# safeguard.net
KiCad netlist of a schematic drawn in EAGLE
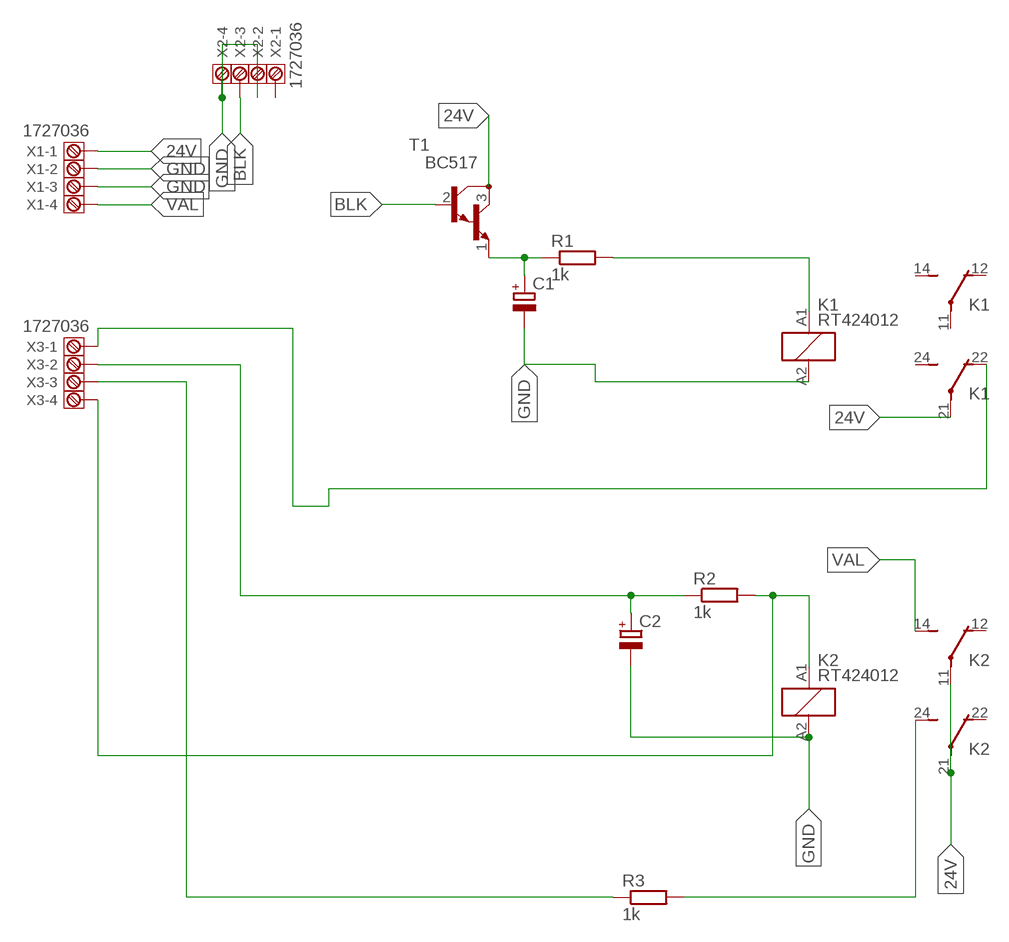
[diagram p0: schematic, sheet 1]

(export (version "E")
  (design (tool "Eeschema 10.0.6"))
  (components
    (comp (ref "C1")
      (value "CPOL-EU153CLV-0405")
      (footprint "eagle-import:153CLV-0405")
      (libsource (lib "eagle-import") (part "CPOL-EU153CLV-0405"))
    )
    (comp (ref "C2")
      (value "CPOL-EU153CLV-0405")
      (footprint "eagle-import:153CLV-0405")
      (libsource (lib "eagle-import") (part "CPOL-EU153CLV-0405"))
    )
    (comp (ref "K1")
      (value "RT424012")
      (footprint "eagle-import:RT2C_O")
      (libsource (lib "eagle-import") (part "RT42?4012"))
    )
    (comp (ref "K2")
      (value "RT424012")
      (footprint "eagle-import:RT2C_O")
      (libsource (lib "eagle-import") (part "RT42?4012"))
    )
    (comp (ref "R1")
      (value "1k")
      (footprint "eagle-import:0204_7")
      (libsource (lib "eagle-import") (part "R-EU_0204/7"))
    )
    (comp (ref "R2")
      (value "1k")
      (footprint "eagle-import:0204_7")
      (libsource (lib "eagle-import") (part "R-EU_0204/7"))
    )
    (comp (ref "R3")
      (value "1k")
      (footprint "eagle-import:0204_7")
      (libsource (lib "eagle-import") (part "R-EU_0204/7"))
    )
    (comp (ref "T1")
      (value "BC517")
      (footprint "eagle-import:TO92")
      (libsource (lib "eagle-import") (part "BC517"))
    )
    (comp (ref "X1")
      (value "1727036")
      (footprint "eagle-import:1727036")
      (fields (field (name "MF") "FARNELL"))
      (libsource (lib "eagle-import") (part "1727036"))
    )
    (comp (ref "X2")
      (value "1727036")
      (footprint "eagle-import:1727036")
      (fields (field (name "MF") "FARNELL"))
      (libsource (lib "eagle-import") (part "1727036"))
    )
    (comp (ref "X3")
      (value "1727036")
      (footprint "eagle-import:1727036")
      (fields (field (name "MF") "FARNELL"))
      (libsource (lib "eagle-import") (part "1727036"))
    )
  )
  (nets
    (net (code "1") (name "24V") (class "Default")
      (node (ref "K1") (pin "21") (pinfunction "P_21") (pintype "passive"))
      (node (ref "K2") (pin "11") (pinfunction "P_11") (pintype "passive"))
      (node (ref "K2") (pin "21") (pinfunction "P_21") (pintype "passive"))
      (node (ref "T1") (pin "3") (pinfunction "C_3") (pintype "passive"))
      (node (ref "X1") (pin "1") (pinfunction "1_1") (pintype "passive"))
    )
    (net (code "2") (name "BLK") (class "Default")
      (node (ref "T1") (pin "2") (pinfunction "B_2") (pintype "passive"))
      (node (ref "X2") (pin "3") (pinfunction "1_3") (pintype "passive"))
    )
    (net (code "3") (name "GND") (class "Default")
      (node (ref "C1") (pin "-") (pinfunction "-_-") (pintype "passive"))
      (node (ref "C2") (pin "-") (pinfunction "-_-") (pintype "passive"))
      (node (ref "K1") (pin "A2") (pinfunction "2_A2") (pintype "passive"))
      (node (ref "K2") (pin "A2") (pinfunction "2_A2") (pintype "passive"))
      (node (ref "X1") (pin "2") (pinfunction "1_2") (pintype "passive"))
      (node (ref "X1") (pin "3") (pinfunction "1_3") (pintype "passive"))
      (node (ref "X2") (pin "2") (pinfunction "1_2") (pintype "passive"))
      (node (ref "X2") (pin "4") (pinfunction "1_4") (pintype "passive"))
    )
    (net (code "4") (name "Net-(K1A-1)") (class "Default")
      (node (ref "K1") (pin "A1") (pinfunction "1_A1") (pintype "passive"))
      (node (ref "R1") (pin "2") (pinfunction "2_2") (pintype "passive"))
    )
    (net (code "5") (name "Net-(K1C-O)") (class "Default")
      (node (ref "K1") (pin "22") (pinfunction "O_22") (pintype "passive"))
      (node (ref "X3") (pin "1") (pinfunction "1_1") (pintype "passive"))
    )
    (net (code "6") (name "Net-(K2A-1)") (class "Default")
      (node (ref "K2") (pin "A1") (pinfunction "1_A1") (pintype "passive"))
      (node (ref "R2") (pin "2") (pinfunction "2_2") (pintype "passive"))
      (node (ref "X3") (pin "4") (pinfunction "1_4") (pintype "passive"))
    )
    (net (code "7") (name "Net-(K2C-S)") (class "Default")
      (node (ref "K2") (pin "24") (pinfunction "S_24") (pintype "passive"))
      (node (ref "R3") (pin "2") (pinfunction "2_2") (pintype "passive"))
    )
    (net (code "8") (name "Net-(T1-E)") (class "Default")
      (node (ref "C1") (pin "+") (pinfunction "+_+") (pintype "passive"))
      (node (ref "R1") (pin "1") (pinfunction "1_1") (pintype "passive"))
      (node (ref "T1") (pin "1") (pinfunction "E_1") (pintype "passive"))
    )
    (net (code "9") (name "Net-(X3B-1)") (class "Default")
      (node (ref "C2") (pin "+") (pinfunction "+_+") (pintype "passive"))
      (node (ref "R2") (pin "1") (pinfunction "1_1") (pintype "passive"))
      (node (ref "X3") (pin "2") (pinfunction "1_2") (pintype "passive"))
    )
    (net (code "10") (name "Net-(X3C-1)") (class "Default")
      (node (ref "R3") (pin "1") (pinfunction "1_1") (pintype "passive"))
      (node (ref "X3") (pin "3") (pinfunction "1_3") (pintype "passive"))
    )
    (net (code "11") (name "VAL") (class "Default")
      (node (ref "K2") (pin "14") (pinfunction "S_14") (pintype "passive"))
      (node (ref "X1") (pin "4") (pinfunction "1_4") (pintype "passive"))
    )
    (net (code "12") (name "unconnected-(K1B-O-Pad12)") (class "Default")
      (node (ref "K1") (pin "12") (pinfunction "O_12") (pintype "passive"))
    )
    (net (code "13") (name "unconnected-(K1B-P-Pad11)") (class "Default")
      (node (ref "K1") (pin "11") (pinfunction "P_11") (pintype "passive"))
    )
    (net (code "14") (name "unconnected-(K1B-S-Pad14)") (class "Default")
      (node (ref "K1") (pin "14") (pinfunction "S_14") (pintype "passive"))
    )
    (net (code "15") (name "unconnected-(K1C-S-Pad24)") (class "Default")
      (node (ref "K1") (pin "24") (pinfunction "S_24") (pintype "passive"))
    )
    (net (code "16") (name "unconnected-(K2B-O-Pad12)") (class "Default")
      (node (ref "K2") (pin "12") (pinfunction "O_12") (pintype "passive"))
    )
    (net (code "17") (name "unconnected-(K2C-O-Pad22)") (class "Default")
      (node (ref "K2") (pin "22") (pinfunction "O_22") (pintype "passive"))
    )
    (net (code "18") (name "unconnected-(X2-Pad1)") (class "Default")
      (node (ref "X2") (pin "1") (pinfunction "1_1") (pintype "passive"))
    )
  )
)
